# fletchstepperjumper1.net
KiCad netlist of a schematic drawn in EAGLE
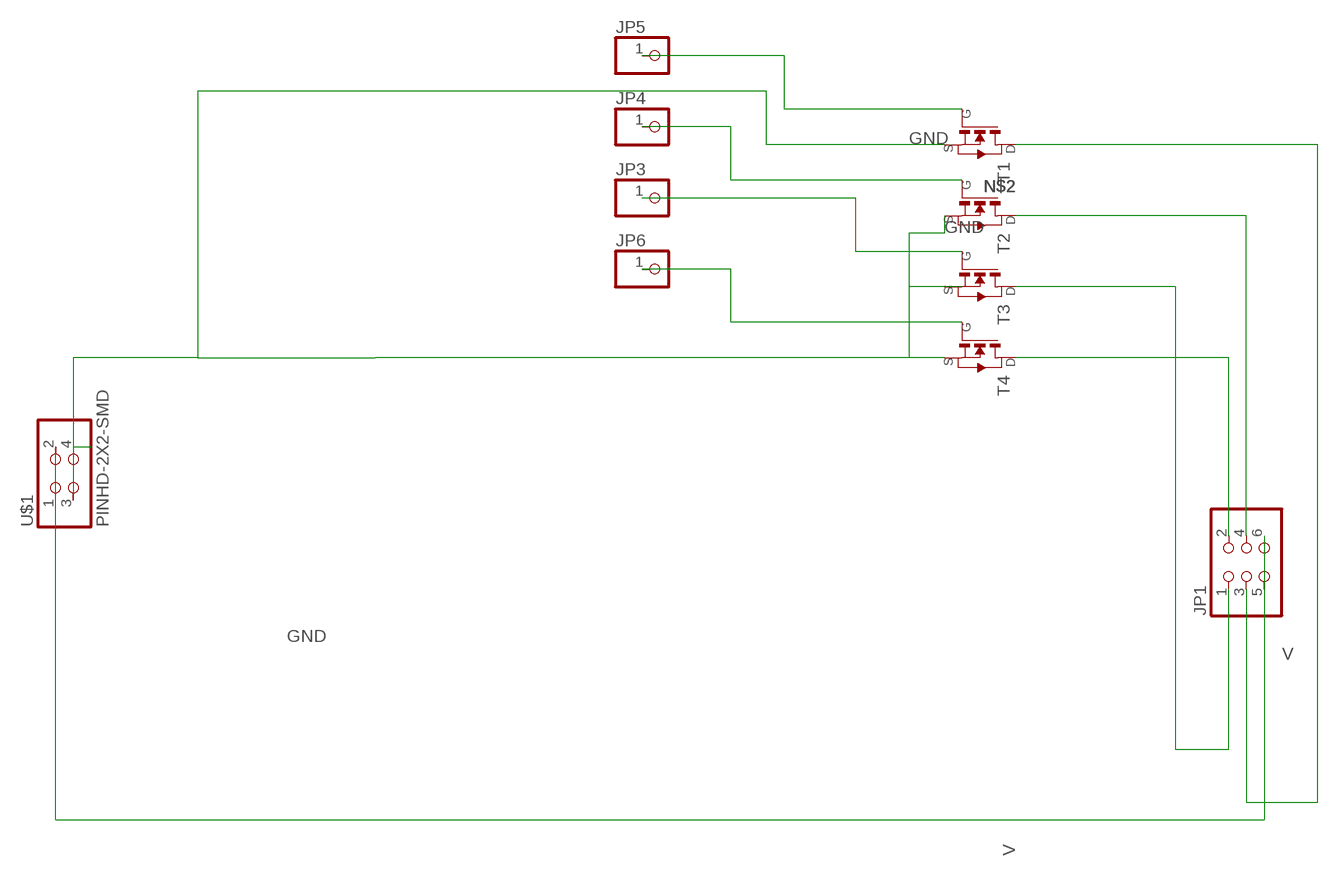
[diagram p0: schematic, sheet 1]

(export (version "E")
  (design (tool "Eeschema 10.0.6"))
  (components
    (comp (ref "JP1")
      (value "PINHD-2X3-SMD")
      (footprint "eagle-import:2X03SMD")
      (libsource (lib "eagle-import") (part "PINHD-2X3-SMD"))
    )
    (comp (ref "JP3")
      (value "PINHD-1X1")
      (footprint "eagle-import:1X01")
      (libsource (lib "eagle-import") (part "PINHD-1X1"))
    )
    (comp (ref "JP4")
      (value "PINHD-1X1")
      (footprint "eagle-import:1X01")
      (libsource (lib "eagle-import") (part "PINHD-1X1"))
    )
    (comp (ref "JP5")
      (value "PINHD-1X1")
      (footprint "eagle-import:1X01")
      (libsource (lib "eagle-import") (part "PINHD-1X1"))
    )
    (comp (ref "JP6")
      (value "PINHD-1X1")
      (footprint "eagle-import:1X01")
      (libsource (lib "eagle-import") (part "PINHD-1X1"))
    )
    (comp (ref "T1")
      (value "NMOSFETSOT23")
      (footprint "eagle-import:SOT-23")
      (libsource (lib "eagle-import") (part "NMOSFETSOT23"))
    )
    (comp (ref "T2")
      (value "NMOSFETSOT23")
      (footprint "eagle-import:SOT-23")
      (libsource (lib "eagle-import") (part "NMOSFETSOT23"))
    )
    (comp (ref "T3")
      (value "NMOSFETSOT23")
      (footprint "eagle-import:SOT-23")
      (libsource (lib "eagle-import") (part "NMOSFETSOT23"))
    )
    (comp (ref "T4")
      (value "NMOSFETSOT23")
      (footprint "eagle-import:SOT-23")
      (libsource (lib "eagle-import") (part "NMOSFETSOT23"))
    )
    (comp (ref "U$1")
      (value "PINHD-2X2-SMD")
      (footprint "eagle-import:2X02SMD")
      (libsource (lib "eagle-import") (part "PINHD-2X2-SMD"))
    )
  )
  (nets
    (net (code "1") (name "/GND") (class "Default")
      (node (ref "T1") (pin "2") (pinfunction "S_2") (pintype "passive"))
      (node (ref "T2") (pin "2") (pinfunction "S_2") (pintype "passive"))
      (node (ref "T4") (pin "2") (pinfunction "S_2") (pintype "passive"))
      (node (ref "U$1") (pin "3") (pinfunction "3_3") (pintype "passive"))
    )
    (net (code "2") (name "/N$2") (class "Default")
      (node (ref "JP4") (pin "1") (pinfunction "1_1") (pintype "passive"))
      (node (ref "T2") (pin "3") (pinfunction "G_3") (pintype "passive"))
    )
    (net (code "3") (name "/V") (class "Default")
      (node (ref "JP1") (pin "5") (pinfunction "5_5") (pintype "passive"))
      (node (ref "JP1") (pin "6") (pinfunction "6_6") (pintype "passive"))
      (node (ref "U$1") (pin "1") (pinfunction "1_1") (pintype "passive"))
      (node (ref "U$1") (pin "2") (pinfunction "2_2") (pintype "passive"))
    )
    (net (code "4") (name "Net-(T1-D)") (class "Default")
      (node (ref "JP1") (pin "3") (pinfunction "3_3") (pintype "passive"))
      (node (ref "T1") (pin "1") (pinfunction "D_1") (pintype "passive"))
    )
    (net (code "5") (name "Net-(T1-G)") (class "Default")
      (node (ref "JP5") (pin "1") (pinfunction "1_1") (pintype "passive"))
      (node (ref "T1") (pin "3") (pinfunction "G_3") (pintype "passive"))
    )
    (net (code "6") (name "Net-(T2-D)") (class "Default")
      (node (ref "JP1") (pin "4") (pinfunction "4_4") (pintype "passive"))
      (node (ref "T2") (pin "1") (pinfunction "D_1") (pintype "passive"))
    )
    (net (code "7") (name "Net-(T3-D)") (class "Default")
      (node (ref "JP1") (pin "1") (pinfunction "1_1") (pintype "passive"))
      (node (ref "T3") (pin "1") (pinfunction "D_1") (pintype "passive"))
    )
    (net (code "8") (name "Net-(T3-G)") (class "Default")
      (node (ref "JP3") (pin "1") (pinfunction "1_1") (pintype "passive"))
      (node (ref "T3") (pin "3") (pinfunction "G_3") (pintype "passive"))
    )
    (net (code "9") (name "Net-(T4-D)") (class "Default")
      (node (ref "JP1") (pin "2") (pinfunction "2_2") (pintype "passive"))
      (node (ref "T4") (pin "1") (pinfunction "D_1") (pintype "passive"))
    )
    (net (code "10") (name "Net-(T4-G)") (class "Default")
      (node (ref "JP6") (pin "1") (pinfunction "1_1") (pintype "passive"))
      (node (ref "T4") (pin "3") (pinfunction "G_3") (pintype "passive"))
    )
    (net (code "11") (name "unconnected-(T3-S-Pad2)") (class "Default")
      (node (ref "T3") (pin "2") (pinfunction "S_2") (pintype "passive"))
    )
    (net (code "12") (name "unconnected-(U$1-Pad4)") (class "Default")
      (node (ref "U$1") (pin "4") (pinfunction "4_4") (pintype "passive"))
    )
  )
)
